# PCB-PWR-FP-35-1_1-in-wall-IoT-FilPilote-.net
KiCad netlist of a schematic drawn in EAGLE
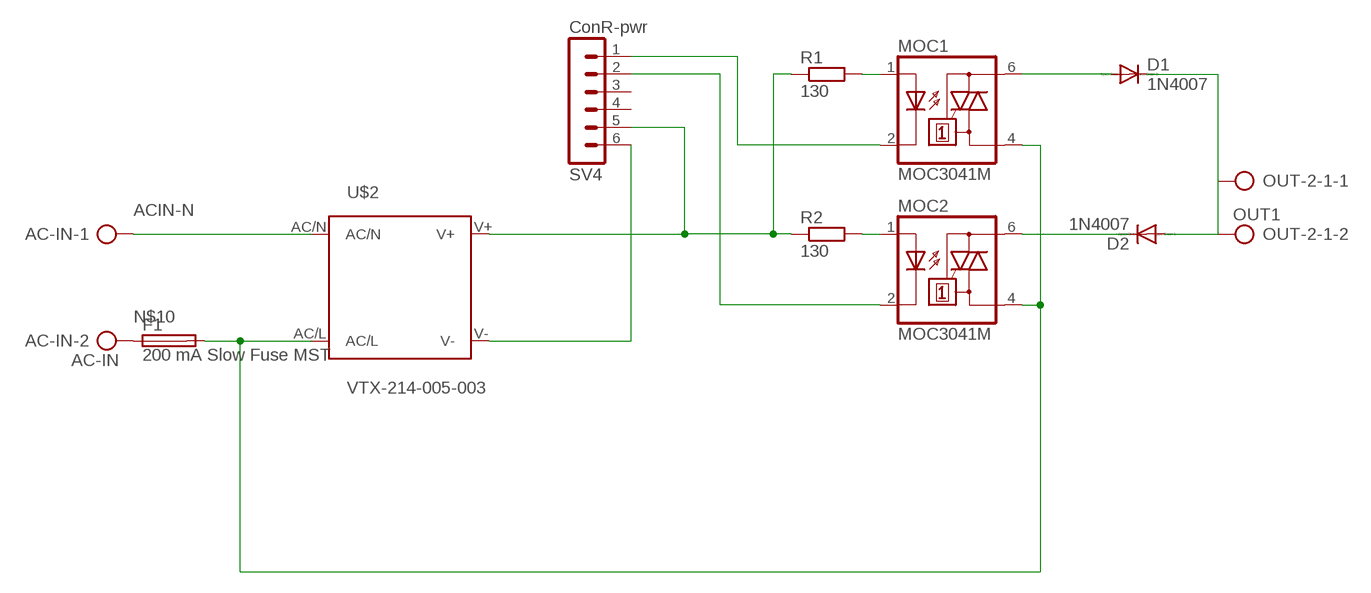
[diagram p0: schematic, sheet 1]

(export (version "E")
  (design (tool "Eeschema 10.0.6"))
  (components
    (comp (ref "AC-IN")
      (value "AC-IN")
      (footprint "eagle-import:AK500_2-H")
      (libsource (lib "eagle-import") (part "AK500/2-H"))
    )
    (comp (ref "D1")
      (value "1N4007")
      (footprint "eagle-import:DO41-10")
      (libsource (lib "eagle-import") (part "1N4004"))
    )
    (comp (ref "D2")
      (value "1N4007")
      (footprint "eagle-import:DO41-10")
      (libsource (lib "eagle-import") (part "1N4004"))
    )
    (comp (ref "F1")
      (value "200 mA Slow Fuse MST")
      (footprint "eagle-import:TE5")
      (libsource (lib "eagle-import") (part "FUSETE5"))
    )
    (comp (ref "MOC1")
      (value "MOC3041M")
      (footprint "eagle-import:DIL06")
      (fields (field (name "MF") "FAIRCHILD SEMICONDUCTOR"))
      (libsource (lib "eagle-import") (part "MOC3041M"))
    )
    (comp (ref "MOC2")
      (value "MOC3041M")
      (footprint "eagle-import:DIL06")
      (fields (field (name "MF") "FAIRCHILD SEMICONDUCTOR"))
      (libsource (lib "eagle-import") (part "MOC3041M"))
    )
    (comp (ref "OUT-2-1")
      (value "OUT1")
      (footprint "eagle-import:AK500_2-H")
      (libsource (lib "eagle-import") (part "AK500/2-H"))
    )
    (comp (ref "R1")
      (value "130")
      (footprint "eagle-import:R1206W")
      (libsource (lib "eagle-import") (part "R-EU_R1206W"))
    )
    (comp (ref "R2")
      (value "130")
      (footprint "eagle-import:R1206W")
      (libsource (lib "eagle-import") (part "R-EU_R1206W"))
    )
    (comp (ref "SV4")
      (value "ConR-pwr")
      (footprint "eagle-import:MA06-1")
      (libsource (lib "eagle-import") (part "MA06-1"))
    )
    (comp (ref "U$2")
      (value "VTX-214-005-003")
      (footprint "eagle-import:VTX-214-005-003")
      (libsource (lib "eagle-import") (part "VTX-214-005-003"))
    )
  )
  (nets
    (net (code "1") (name "/ACIN-N") (class "Default")
      (node (ref "AC-IN") (pin "1") (pinfunction "KL_1") (pintype "passive"))
      (node (ref "U$2") (pin "AC/N") (pinfunction "AC/N_AC/N") (pintype "input"))
    )
    (net (code "3") (name "Net-(AC-INB-KL)") (class "Default")
      (node (ref "AC-IN") (pin "2") (pinfunction "KL_2") (pintype "passive"))
      (node (ref "F1") (pin "1") (pinfunction "1_1") (pintype "passive"))
    )
    (net (code "4") (name "Net-(MOC1-A)") (class "Default")
      (node (ref "MOC1") (pin "1") (pinfunction "A_1") (pintype "passive"))
      (node (ref "R1") (pin "2") (pinfunction "2_2") (pintype "passive"))
    )
    (net (code "5") (name "Net-(MOC1-A1)") (class "Default")
      (node (ref "F1") (pin "2") (pinfunction "2_2") (pintype "passive"))
      (node (ref "MOC1") (pin "4") (pinfunction "A1_4") (pintype "passive"))
      (node (ref "MOC2") (pin "4") (pinfunction "A1_4") (pintype "passive"))
      (node (ref "U$2") (pin "AC/L") (pinfunction "AC/L_AC/L") (pintype "input"))
    )
    (net (code "6") (name "Net-(MOC1-A2)") (class "Default")
      (node (ref "D1") (pin "A") (pinfunction "A_A") (pintype "passive"))
      (node (ref "MOC1") (pin "6") (pinfunction "A2_6") (pintype "passive"))
    )
    (net (code "7") (name "Net-(MOC1-C)") (class "Default")
      (node (ref "MOC1") (pin "2") (pinfunction "C_2") (pintype "passive"))
      (node (ref "SV4") (pin "1") (pinfunction "1_1") (pintype "passive"))
    )
    (net (code "8") (name "Net-(MOC2-A)") (class "Default")
      (node (ref "MOC2") (pin "1") (pinfunction "A_1") (pintype "passive"))
      (node (ref "R2") (pin "2") (pinfunction "2_2") (pintype "passive"))
    )
    (net (code "9") (name "Net-(MOC2-A2)") (class "Default")
      (node (ref "D2") (pin "C") (pinfunction "C_C") (pintype "passive"))
      (node (ref "MOC2") (pin "6") (pinfunction "A2_6") (pintype "passive"))
    )
    (net (code "10") (name "Net-(MOC2-C)") (class "Default")
      (node (ref "MOC2") (pin "2") (pinfunction "C_2") (pintype "passive"))
      (node (ref "SV4") (pin "2") (pinfunction "2_2") (pintype "passive"))
    )
    (net (code "11") (name "Net-(OUT-2-1A-KL)") (class "Default")
      (node (ref "D1") (pin "C") (pinfunction "C_C") (pintype "passive"))
      (node (ref "D2") (pin "A") (pinfunction "A_A") (pintype "passive"))
      (node (ref "OUT-2-1") (pin "1") (pinfunction "KL_1") (pintype "passive"))
      (node (ref "OUT-2-1") (pin "2") (pinfunction "KL_2") (pintype "passive"))
    )
    (net (code "12") (name "Net-(R1-Pad1)") (class "Default")
      (node (ref "R1") (pin "1") (pinfunction "1_1") (pintype "passive"))
      (node (ref "R2") (pin "1") (pinfunction "1_1") (pintype "passive"))
      (node (ref "SV4") (pin "5") (pinfunction "5_5") (pintype "passive"))
      (node (ref "U$2") (pin "V+") (pinfunction "V+_V+") (pintype "output"))
    )
    (net (code "13") (name "Net-(SV4-Pad6)") (class "Default")
      (node (ref "SV4") (pin "6") (pinfunction "6_6") (pintype "passive"))
      (node (ref "U$2") (pin "V-") (pinfunction "V-_V-") (pintype "output"))
    )
    (net (code "14") (name "unconnected-(SV4-Pad3)") (class "Default")
      (node (ref "SV4") (pin "3") (pinfunction "3_3") (pintype "passive"))
    )
    (net (code "15") (name "unconnected-(SV4-Pad4)") (class "Default")
      (node (ref "SV4") (pin "4") (pinfunction "4_4") (pintype "passive"))
    )
  )
)
